# dome-board3.net
KiCad netlist of a schematic drawn in EAGLE
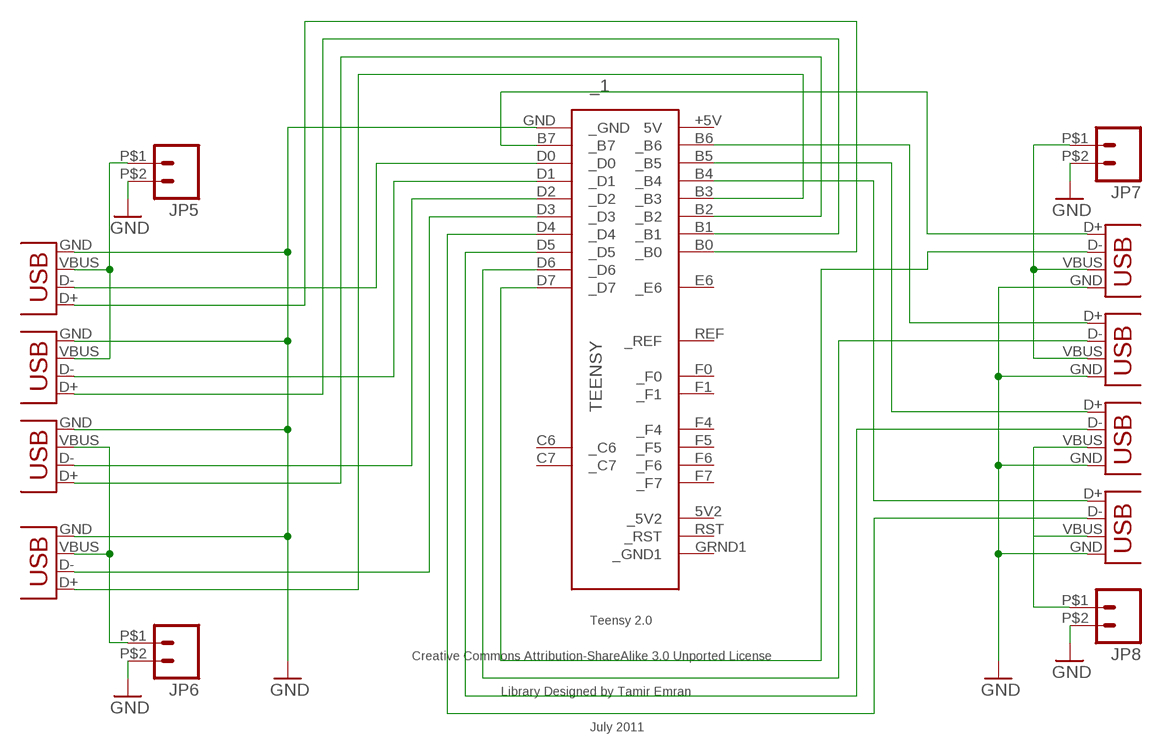
[diagram p0: schematic, sheet 1]

(export (version "E")
  (design (tool "Eeschema 10.0.6"))
  (components
    (comp (ref "JP5")
      (value "M026.35MM")
      (footprint "eagle-import:SCREWTERMINAL-6.35MM-2")
      (libsource (lib "eagle-import") (part "M026.35MM"))
    )
    (comp (ref "JP6")
      (value "M026.35MM")
      (footprint "eagle-import:SCREWTERMINAL-6.35MM-2")
      (libsource (lib "eagle-import") (part "M026.35MM"))
    )
    (comp (ref "JP7")
      (value "M026.35MM")
      (footprint "eagle-import:SCREWTERMINAL-6.35MM-2")
      (libsource (lib "eagle-import") (part "M026.35MM"))
    )
    (comp (ref "JP8")
      (value "M026.35MM")
      (footprint "eagle-import:SCREWTERMINAL-6.35MM-2")
      (libsource (lib "eagle-import") (part "M026.35MM"))
    )
    (comp (ref "USB1")
      (value "USB")
      (footprint "eagle-import:USBA")
      (libsource (lib "eagle-import") (part "USB"))
    )
    (comp (ref "USB2")
      (value "USB")
      (footprint "eagle-import:USBA")
      (libsource (lib "eagle-import") (part "USB"))
    )
    (comp (ref "USB3")
      (value "USB")
      (footprint "eagle-import:USBA")
      (libsource (lib "eagle-import") (part "USB"))
    )
    (comp (ref "USB4")
      (value "USB")
      (footprint "eagle-import:USBA")
      (libsource (lib "eagle-import") (part "USB"))
    )
    (comp (ref "USB5")
      (value "USB")
      (footprint "eagle-import:USBA")
      (libsource (lib "eagle-import") (part "USB"))
    )
    (comp (ref "USB6")
      (value "USB")
      (footprint "eagle-import:USBA")
      (libsource (lib "eagle-import") (part "USB"))
    )
    (comp (ref "USB7")
      (value "USB")
      (footprint "eagle-import:USBA")
      (libsource (lib "eagle-import") (part "USB"))
    )
    (comp (ref "USB8")
      (value "USB")
      (footprint "eagle-import:USBA")
      (libsource (lib "eagle-import") (part "USB"))
    )
    (comp (ref "_1")
      (value "TEENSY")
      (footprint "eagle-import:TEENSY")
      (libsource (lib "eagle-import") (part "TEENSY"))
    )
  )
  (nets
    (net (code "1") (name "GND") (class "Default")
      (node (ref "JP5") (pin "P$2") (pinfunction "2_P$2") (pintype "passive"))
      (node (ref "JP6") (pin "P$2") (pinfunction "2_P$2") (pintype "passive"))
      (node (ref "JP7") (pin "P$2") (pinfunction "2_P$2") (pintype "passive"))
      (node (ref "JP8") (pin "P$2") (pinfunction "2_P$2") (pintype "passive"))
      (node (ref "USB1") (pin "GND") (pinfunction "GND_GND") (pintype "bidirectional"))
      (node (ref "USB2") (pin "GND") (pinfunction "GND_GND") (pintype "bidirectional"))
      (node (ref "USB3") (pin "GND") (pinfunction "GND_GND") (pintype "bidirectional"))
      (node (ref "USB4") (pin "GND") (pinfunction "GND_GND") (pintype "bidirectional"))
      (node (ref "USB5") (pin "GND") (pinfunction "GND_GND") (pintype "bidirectional"))
      (node (ref "USB6") (pin "GND") (pinfunction "GND_GND") (pintype "bidirectional"))
      (node (ref "USB7") (pin "GND") (pinfunction "GND_GND") (pintype "bidirectional"))
      (node (ref "USB8") (pin "GND") (pinfunction "GND_GND") (pintype "bidirectional"))
      (node (ref "_1") (pin "GND") (pinfunction "_GND_GND") (pintype "bidirectional"))
    )
    (net (code "2") (name "Net-(JP5-1)") (class "Default")
      (node (ref "JP5") (pin "P$1") (pinfunction "1_P$1") (pintype "passive"))
      (node (ref "USB1") (pin "VBUS") (pinfunction "VBUS_VBUS") (pintype "bidirectional"))
      (node (ref "USB2") (pin "VBUS") (pinfunction "VBUS_VBUS") (pintype "bidirectional"))
    )
    (net (code "3") (name "Net-(JP6-1)") (class "Default")
      (node (ref "JP6") (pin "P$1") (pinfunction "1_P$1") (pintype "passive"))
      (node (ref "USB3") (pin "VBUS") (pinfunction "VBUS_VBUS") (pintype "bidirectional"))
      (node (ref "USB4") (pin "VBUS") (pinfunction "VBUS_VBUS") (pintype "bidirectional"))
    )
    (net (code "4") (name "Net-(JP7-1)") (class "Default")
      (node (ref "JP7") (pin "P$1") (pinfunction "1_P$1") (pintype "passive"))
      (node (ref "USB7") (pin "VBUS") (pinfunction "VBUS_VBUS") (pintype "bidirectional"))
      (node (ref "USB8") (pin "VBUS") (pinfunction "VBUS_VBUS") (pintype "bidirectional"))
    )
    (net (code "5") (name "Net-(JP8-1)") (class "Default")
      (node (ref "JP8") (pin "P$1") (pinfunction "1_P$1") (pintype "passive"))
      (node (ref "USB5") (pin "VBUS") (pinfunction "VBUS_VBUS") (pintype "bidirectional"))
      (node (ref "USB6") (pin "VBUS") (pinfunction "VBUS_VBUS") (pintype "bidirectional"))
    )
    (net (code "6") (name "Net-(_1-_B0)") (class "Default")
      (node (ref "USB1") (pin "D+") (pinfunction "D+_D+") (pintype "bidirectional"))
      (node (ref "_1") (pin "B0") (pinfunction "_B0_B0") (pintype "bidirectional"))
    )
    (net (code "7") (name "Net-(_1-_B1)") (class "Default")
      (node (ref "USB2") (pin "D+") (pinfunction "D+_D+") (pintype "bidirectional"))
      (node (ref "_1") (pin "B1") (pinfunction "_B1_B1") (pintype "bidirectional"))
    )
    (net (code "8") (name "Net-(_1-_B2)") (class "Default")
      (node (ref "USB3") (pin "D+") (pinfunction "D+_D+") (pintype "bidirectional"))
      (node (ref "_1") (pin "B2") (pinfunction "_B2_B2") (pintype "bidirectional"))
    )
    (net (code "9") (name "Net-(_1-_B3)") (class "Default")
      (node (ref "USB4") (pin "D+") (pinfunction "D+_D+") (pintype "bidirectional"))
      (node (ref "_1") (pin "B3") (pinfunction "_B3_B3") (pintype "bidirectional"))
    )
    (net (code "10") (name "Net-(_1-_B4)") (class "Default")
      (node (ref "USB5") (pin "D+") (pinfunction "D+_D+") (pintype "bidirectional"))
      (node (ref "_1") (pin "B4") (pinfunction "_B4_B4") (pintype "bidirectional"))
    )
    (net (code "11") (name "Net-(_1-_B5)") (class "Default")
      (node (ref "USB6") (pin "D+") (pinfunction "D+_D+") (pintype "bidirectional"))
      (node (ref "_1") (pin "B5") (pinfunction "_B5_B5") (pintype "bidirectional"))
    )
    (net (code "12") (name "Net-(_1-_B6)") (class "Default")
      (node (ref "USB7") (pin "D+") (pinfunction "D+_D+") (pintype "bidirectional"))
      (node (ref "_1") (pin "B6") (pinfunction "_B6_B6") (pintype "bidirectional"))
    )
    (net (code "13") (name "Net-(_1-_B7)") (class "Default")
      (node (ref "USB8") (pin "D+") (pinfunction "D+_D+") (pintype "bidirectional"))
      (node (ref "_1") (pin "B7") (pinfunction "_B7_B7") (pintype "bidirectional"))
    )
    (net (code "14") (name "Net-(_1-_D0)") (class "Default")
      (node (ref "USB1") (pin "D-") (pinfunction "D-_D-") (pintype "bidirectional"))
      (node (ref "_1") (pin "D0") (pinfunction "_D0_D0") (pintype "bidirectional"))
    )
    (net (code "15") (name "Net-(_1-_D1)") (class "Default")
      (node (ref "USB2") (pin "D-") (pinfunction "D-_D-") (pintype "bidirectional"))
      (node (ref "_1") (pin "D1") (pinfunction "_D1_D1") (pintype "bidirectional"))
    )
    (net (code "16") (name "Net-(_1-_D2)") (class "Default")
      (node (ref "USB3") (pin "D-") (pinfunction "D-_D-") (pintype "bidirectional"))
      (node (ref "_1") (pin "D2") (pinfunction "_D2_D2") (pintype "bidirectional"))
    )
    (net (code "17") (name "Net-(_1-_D3)") (class "Default")
      (node (ref "USB4") (pin "D-") (pinfunction "D-_D-") (pintype "bidirectional"))
      (node (ref "_1") (pin "D3") (pinfunction "_D3_D3") (pintype "bidirectional"))
    )
    (net (code "18") (name "Net-(_1-_D4)") (class "Default")
      (node (ref "USB5") (pin "D-") (pinfunction "D-_D-") (pintype "bidirectional"))
      (node (ref "_1") (pin "D4") (pinfunction "_D4_D4") (pintype "bidirectional"))
    )
    (net (code "19") (name "Net-(_1-_D5)") (class "Default")
      (node (ref "USB6") (pin "D-") (pinfunction "D-_D-") (pintype "bidirectional"))
      (node (ref "_1") (pin "D5") (pinfunction "_D5_D5") (pintype "bidirectional"))
    )
    (net (code "20") (name "Net-(_1-_D6)") (class "Default")
      (node (ref "USB7") (pin "D-") (pinfunction "D-_D-") (pintype "bidirectional"))
      (node (ref "_1") (pin "D6") (pinfunction "_D6_D6") (pintype "bidirectional"))
    )
    (net (code "21") (name "Net-(_1-_D7)") (class "Default")
      (node (ref "USB8") (pin "D-") (pinfunction "D-_D-") (pintype "bidirectional"))
      (node (ref "_1") (pin "D7") (pinfunction "_D7_D7") (pintype "bidirectional"))
    )
    (net (code "22") (name "unconnected-(_1-5V-Pad+5V)") (class "Default")
      (node (ref "_1") (pin "+5V") (pinfunction "5V_+5V") (pintype "bidirectional"))
    )
    (net (code "23") (name "unconnected-(_1-_5V2-Pad5V2)") (class "Default")
      (node (ref "_1") (pin "5V2") (pinfunction "_5V2_5V2") (pintype "bidirectional"))
    )
    (net (code "24") (name "unconnected-(_1-_C6-PadC6)") (class "Default")
      (node (ref "_1") (pin "C6") (pinfunction "_C6_C6") (pintype "bidirectional"))
    )
    (net (code "25") (name "unconnected-(_1-_C7-PadC7)") (class "Default")
      (node (ref "_1") (pin "C7") (pinfunction "_C7_C7") (pintype "bidirectional"))
    )
    (net (code "26") (name "unconnected-(_1-_E6-PadE6)") (class "Default")
      (node (ref "_1") (pin "E6") (pinfunction "_E6_E6") (pintype "bidirectional"))
    )
    (net (code "27") (name "unconnected-(_1-_F0-PadF0)") (class "Default")
      (node (ref "_1") (pin "F0") (pinfunction "_F0_F0") (pintype "bidirectional"))
    )
    (net (code "28") (name "unconnected-(_1-_F1-PadF1)") (class "Default")
      (node (ref "_1") (pin "F1") (pinfunction "_F1_F1") (pintype "bidirectional"))
    )
    (net (code "29") (name "unconnected-(_1-_F4-PadF4)") (class "Default")
      (node (ref "_1") (pin "F4") (pinfunction "_F4_F4") (pintype "bidirectional"))
    )
    (net (code "30") (name "unconnected-(_1-_F5-PadF5)") (class "Default")
      (node (ref "_1") (pin "F5") (pinfunction "_F5_F5") (pintype "bidirectional"))
    )
    (net (code "31") (name "unconnected-(_1-_F6-PadF6)") (class "Default")
      (node (ref "_1") (pin "F6") (pinfunction "_F6_F6") (pintype "bidirectional"))
    )
    (net (code "32") (name "unconnected-(_1-_F7-PadF7)") (class "Default")
      (node (ref "_1") (pin "F7") (pinfunction "_F7_F7") (pintype "bidirectional"))
    )
    (net (code "33") (name "unconnected-(_1-_GND1-PadGRND1)") (class "Default")
      (node (ref "_1") (pin "GRND1") (pinfunction "_GND1_GRND1") (pintype "bidirectional"))
    )
    (net (code "34") (name "unconnected-(_1-_REF-PadREF)") (class "Default")
      (node (ref "_1") (pin "REF") (pinfunction "_REF_REF") (pintype "bidirectional"))
    )
    (net (code "35") (name "unconnected-(_1-_RST-PadRST)") (class "Default")
      (node (ref "_1") (pin "RST") (pinfunction "_RST_RST") (pintype "bidirectional"))
    )
  )
)
